# pnuematic_board_rev1.net
KiCad netlist of a schematic drawn in Altium Designer
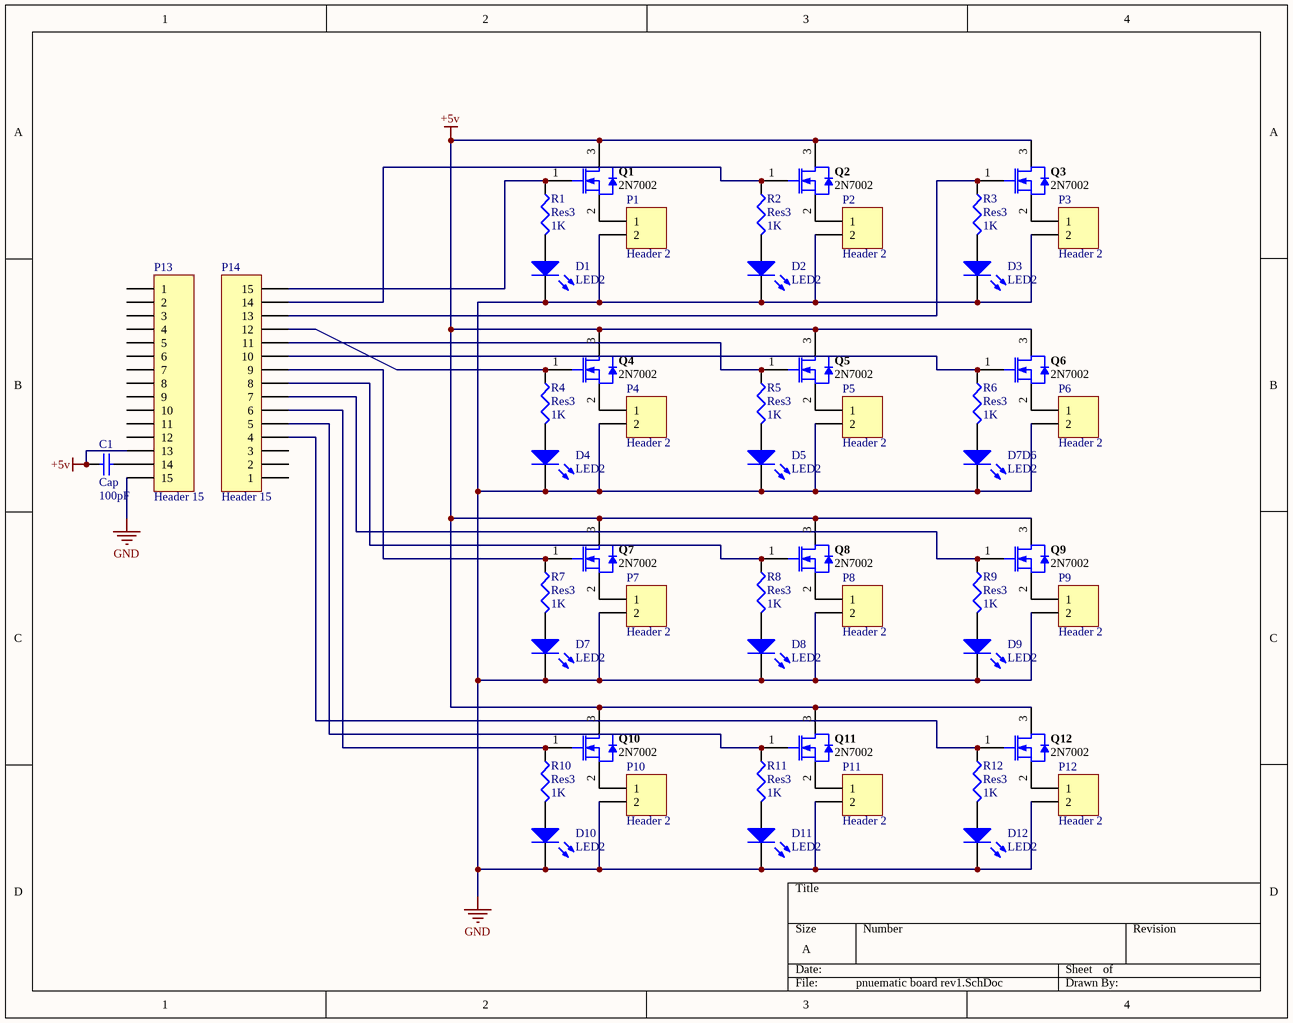
[diagram p0: pnuematic board rev1.SchDoc]

(export (version "E")
  (design (tool "Eeschema 10.0.6"))
  (components
    (comp (ref "C1")
      (value "Cap")
      (footprint "RAD-0.3")
      (description "Capacitor")
      (fields (field (name "ALTIUM_VALUE") "100pF") (field (name "PUBLISHER") "Altium Limited"))
      (libsource (lib "Miscellaneous Devices") (part "Cap"))
    )
    (comp (ref "D1")
      (value "LED2")
      (footprint "3.2X1.6X1.1")
      (description "Typical RED, GREEN, YELLOW, AMBER GaAs LED")
      (fields (field (name "PUBLISHER") "Altium Limited"))
      (libsource (lib "Miscellaneous Devices") (part "LED2"))
    )
    (comp (ref "D2")
      (value "LED2")
      (footprint "3.2X1.6X1.1")
      (description "Typical RED, GREEN, YELLOW, AMBER GaAs LED")
      (fields (field (name "PUBLISHER") "Altium Limited"))
      (libsource (lib "Miscellaneous Devices") (part "LED2"))
    )
    (comp (ref "D3")
      (value "LED2")
      (footprint "3.2X1.6X1.1")
      (description "Typical RED, GREEN, YELLOW, AMBER GaAs LED")
      (fields (field (name "PUBLISHER") "Altium Limited"))
      (libsource (lib "Miscellaneous Devices") (part "LED2"))
    )
    (comp (ref "D4")
      (value "LED2")
      (footprint "3.2X1.6X1.1")
      (description "Typical RED, GREEN, YELLOW, AMBER GaAs LED")
      (fields (field (name "PUBLISHER") "Altium Limited"))
      (libsource (lib "Miscellaneous Devices") (part "LED2"))
    )
    (comp (ref "D5")
      (value "LED2")
      (footprint "3.2X1.6X1.1")
      (description "Typical RED, GREEN, YELLOW, AMBER GaAs LED")
      (fields (field (name "PUBLISHER") "Altium Limited"))
      (libsource (lib "Miscellaneous Devices") (part "LED2"))
    )
    (comp (ref "D7")
      (value "LED2")
      (footprint "3.2X1.6X1.1")
      (description "Typical RED, GREEN, YELLOW, AMBER GaAs LED")
      (fields (field (name "PUBLISHER") "Altium Limited"))
      (libsource (lib "Miscellaneous Devices") (part "LED2"))
    )
    (comp (ref "D7D6")
      (value "LED2")
      (footprint "3.2X1.6X1.1")
      (description "Typical RED, GREEN, YELLOW, AMBER GaAs LED")
      (fields (field (name "PUBLISHER") "Altium Limited"))
      (libsource (lib "Miscellaneous Devices") (part "LED2"))
    )
    (comp (ref "D8")
      (value "LED2")
      (footprint "3.2X1.6X1.1")
      (description "Typical RED, GREEN, YELLOW, AMBER GaAs LED")
      (fields (field (name "PUBLISHER") "Altium Limited"))
      (libsource (lib "Miscellaneous Devices") (part "LED2"))
    )
    (comp (ref "D9")
      (value "LED2")
      (footprint "3.2X1.6X1.1")
      (description "Typical RED, GREEN, YELLOW, AMBER GaAs LED")
      (fields (field (name "PUBLISHER") "Altium Limited"))
      (libsource (lib "Miscellaneous Devices") (part "LED2"))
    )
    (comp (ref "D10")
      (value "LED2")
      (footprint "3.2X1.6X1.1")
      (description "Typical RED, GREEN, YELLOW, AMBER GaAs LED")
      (fields (field (name "PUBLISHER") "Altium Limited"))
      (libsource (lib "Miscellaneous Devices") (part "LED2"))
    )
    (comp (ref "D11")
      (value "LED2")
      (footprint "3.2X1.6X1.1")
      (description "Typical RED, GREEN, YELLOW, AMBER GaAs LED")
      (fields (field (name "PUBLISHER") "Altium Limited"))
      (libsource (lib "Miscellaneous Devices") (part "LED2"))
    )
    (comp (ref "D12")
      (value "LED2")
      (footprint "3.2X1.6X1.1")
      (description "Typical RED, GREEN, YELLOW, AMBER GaAs LED")
      (fields (field (name "PUBLISHER") "Altium Limited"))
      (libsource (lib "Miscellaneous Devices") (part "LED2"))
    )
    (comp (ref "P1")
      (value "Header 2")
      (footprint "HDR1X2")
      (description "Header, 2-Pin")
      (fields (field (name "PUBLISHER") "Altium Limited"))
      (libsource (lib "Miscellaneous Connectors") (part "Header 2"))
    )
    (comp (ref "P2")
      (value "Header 2")
      (footprint "HDR1X2")
      (description "Header, 2-Pin")
      (fields (field (name "PUBLISHER") "Altium Limited"))
      (libsource (lib "Miscellaneous Connectors") (part "Header 2"))
    )
    (comp (ref "P3")
      (value "Header 2")
      (footprint "HDR1X2")
      (description "Header, 2-Pin")
      (fields (field (name "PUBLISHER") "Altium Limited"))
      (libsource (lib "Miscellaneous Connectors") (part "Header 2"))
    )
    (comp (ref "P4")
      (value "Header 2")
      (footprint "HDR1X2")
      (description "Header, 2-Pin")
      (fields (field (name "PUBLISHER") "Altium Limited"))
      (libsource (lib "Miscellaneous Connectors") (part "Header 2"))
    )
    (comp (ref "P5")
      (value "Header 2")
      (footprint "HDR1X2")
      (description "Header, 2-Pin")
      (fields (field (name "PUBLISHER") "Altium Limited"))
      (libsource (lib "Miscellaneous Connectors") (part "Header 2"))
    )
    (comp (ref "P6")
      (value "Header 2")
      (footprint "HDR1X2")
      (description "Header, 2-Pin")
      (fields (field (name "PUBLISHER") "Altium Limited"))
      (libsource (lib "Miscellaneous Connectors") (part "Header 2"))
    )
    (comp (ref "P7")
      (value "Header 2")
      (footprint "HDR1X2")
      (description "Header, 2-Pin")
      (fields (field (name "PUBLISHER") "Altium Limited"))
      (libsource (lib "Miscellaneous Connectors") (part "Header 2"))
    )
    (comp (ref "P8")
      (value "Header 2")
      (footprint "HDR1X2")
      (description "Header, 2-Pin")
      (fields (field (name "PUBLISHER") "Altium Limited"))
      (libsource (lib "Miscellaneous Connectors") (part "Header 2"))
    )
    (comp (ref "P9")
      (value "Header 2")
      (footprint "HDR1X2")
      (description "Header, 2-Pin")
      (fields (field (name "PUBLISHER") "Altium Limited"))
      (libsource (lib "Miscellaneous Connectors") (part "Header 2"))
    )
    (comp (ref "P10")
      (value "Header 2")
      (footprint "HDR1X2")
      (description "Header, 2-Pin")
      (fields (field (name "PUBLISHER") "Altium Limited"))
      (libsource (lib "Miscellaneous Connectors") (part "Header 2"))
    )
    (comp (ref "P11")
      (value "Header 2")
      (footprint "HDR1X2")
      (description "Header, 2-Pin")
      (fields (field (name "PUBLISHER") "Altium Limited"))
      (libsource (lib "Miscellaneous Connectors") (part "Header 2"))
    )
    (comp (ref "P12")
      (value "Header 2")
      (footprint "HDR1X2")
      (description "Header, 2-Pin")
      (fields (field (name "PUBLISHER") "Altium Limited"))
      (libsource (lib "Miscellaneous Connectors") (part "Header 2"))
    )
    (comp (ref "P13")
      (value "Header 15")
      (footprint "HDR1X15")
      (description "Header, 15-Pin")
      (fields (field (name "PUBLISHER") "Altium Limited"))
      (libsource (lib "") (part "Header 15_1"))
    )
    (comp (ref "P14")
      (value "Header 15")
      (footprint "HDR1X15")
      (description "Header, 15-Pin")
      (fields (field (name "PUBLISHER") "Altium Limited"))
      (libsource (lib "Miscellaneous Connectors") (part "Header 15"))
    )
    (comp (ref "Q1")
      (value "2N7002")
      (footprint "INF-PG-SOT23_N")
      (fields (field (name "MANUFACTURER") "Infineon"))
      (libsource (lib "Infineon_Power_MOSFET") (part "2N7002"))
    )
    (comp (ref "Q2")
      (value "2N7002")
      (footprint "INF-PG-SOT23_N")
      (fields (field (name "MANUFACTURER") "Infineon"))
      (libsource (lib "Infineon_Power_MOSFET") (part "2N7002"))
    )
    (comp (ref "Q3")
      (value "2N7002")
      (footprint "INF-PG-SOT23_N")
      (fields (field (name "MANUFACTURER") "Infineon"))
      (libsource (lib "Infineon_Power_MOSFET") (part "2N7002"))
    )
    (comp (ref "Q4")
      (value "2N7002")
      (footprint "INF-PG-SOT23_N")
      (fields (field (name "MANUFACTURER") "Infineon"))
      (libsource (lib "Infineon_Power_MOSFET") (part "2N7002"))
    )
    (comp (ref "Q5")
      (value "2N7002")
      (footprint "INF-PG-SOT23_N")
      (fields (field (name "MANUFACTURER") "Infineon"))
      (libsource (lib "Infineon_Power_MOSFET") (part "2N7002"))
    )
    (comp (ref "Q6")
      (value "2N7002")
      (footprint "INF-PG-SOT23_N")
      (fields (field (name "MANUFACTURER") "Infineon"))
      (libsource (lib "Infineon_Power_MOSFET") (part "2N7002"))
    )
    (comp (ref "Q7")
      (value "2N7002")
      (footprint "INF-PG-SOT23_N")
      (fields (field (name "MANUFACTURER") "Infineon"))
      (libsource (lib "Infineon_Power_MOSFET") (part "2N7002"))
    )
    (comp (ref "Q8")
      (value "2N7002")
      (footprint "INF-PG-SOT23_N")
      (fields (field (name "MANUFACTURER") "Infineon"))
      (libsource (lib "Infineon_Power_MOSFET") (part "2N7002"))
    )
    (comp (ref "Q9")
      (value "2N7002")
      (footprint "INF-PG-SOT23_N")
      (fields (field (name "MANUFACTURER") "Infineon"))
      (libsource (lib "Infineon_Power_MOSFET") (part "2N7002"))
    )
    (comp (ref "Q10")
      (value "2N7002")
      (footprint "INF-PG-SOT23_N")
      (fields (field (name "MANUFACTURER") "Infineon"))
      (libsource (lib "Infineon_Power_MOSFET") (part "2N7002"))
    )
    (comp (ref "Q11")
      (value "2N7002")
      (footprint "INF-PG-SOT23_N")
      (fields (field (name "MANUFACTURER") "Infineon"))
      (libsource (lib "Infineon_Power_MOSFET") (part "2N7002"))
    )
    (comp (ref "Q12")
      (value "2N7002")
      (footprint "INF-PG-SOT23_N")
      (fields (field (name "MANUFACTURER") "Infineon"))
      (libsource (lib "Infineon_Power_MOSFET") (part "2N7002"))
    )
    (comp (ref "R1")
      (value "Res3")
      (footprint "J1-0603")
      (description "Resistor")
      (fields (field (name "ALTIUM_VALUE") "1K") (field (name "PUBLISHER") "Altium Limited"))
      (libsource (lib "Miscellaneous Devices") (part "Res3"))
    )
    (comp (ref "R2")
      (value "Res3")
      (footprint "J1-0603")
      (description "Resistor")
      (fields (field (name "ALTIUM_VALUE") "1K") (field (name "PUBLISHER") "Altium Limited"))
      (libsource (lib "Miscellaneous Devices") (part "Res3"))
    )
    (comp (ref "R3")
      (value "Res3")
      (footprint "J1-0603")
      (description "Resistor")
      (fields (field (name "ALTIUM_VALUE") "1K") (field (name "PUBLISHER") "Altium Limited"))
      (libsource (lib "Miscellaneous Devices") (part "Res3"))
    )
    (comp (ref "R4")
      (value "Res3")
      (footprint "J1-0603")
      (description "Resistor")
      (fields (field (name "ALTIUM_VALUE") "1K") (field (name "PUBLISHER") "Altium Limited"))
      (libsource (lib "Miscellaneous Devices") (part "Res3"))
    )
    (comp (ref "R5")
      (value "Res3")
      (footprint "J1-0603")
      (description "Resistor")
      (fields (field (name "ALTIUM_VALUE") "1K") (field (name "PUBLISHER") "Altium Limited"))
      (libsource (lib "Miscellaneous Devices") (part "Res3"))
    )
    (comp (ref "R6")
      (value "Res3")
      (footprint "J1-0603")
      (description "Resistor")
      (fields (field (name "ALTIUM_VALUE") "1K") (field (name "PUBLISHER") "Altium Limited"))
      (libsource (lib "Miscellaneous Devices") (part "Res3"))
    )
    (comp (ref "R7")
      (value "Res3")
      (footprint "J1-0603")
      (description "Resistor")
      (fields (field (name "ALTIUM_VALUE") "1K") (field (name "PUBLISHER") "Altium Limited"))
      (libsource (lib "Miscellaneous Devices") (part "Res3"))
    )
    (comp (ref "R8")
      (value "Res3")
      (footprint "J1-0603")
      (description "Resistor")
      (fields (field (name "ALTIUM_VALUE") "1K") (field (name "PUBLISHER") "Altium Limited"))
      (libsource (lib "Miscellaneous Devices") (part "Res3"))
    )
    (comp (ref "R9")
      (value "Res3")
      (footprint "J1-0603")
      (description "Resistor")
      (fields (field (name "ALTIUM_VALUE") "1K") (field (name "PUBLISHER") "Altium Limited"))
      (libsource (lib "Miscellaneous Devices") (part "Res3"))
    )
    (comp (ref "R10")
      (value "Res3")
      (footprint "J1-0603")
      (description "Resistor")
      (fields (field (name "ALTIUM_VALUE") "1K") (field (name "PUBLISHER") "Altium Limited"))
      (libsource (lib "Miscellaneous Devices") (part "Res3"))
    )
    (comp (ref "R11")
      (value "Res3")
      (footprint "J1-0603")
      (description "Resistor")
      (fields (field (name "ALTIUM_VALUE") "1K") (field (name "PUBLISHER") "Altium Limited"))
      (libsource (lib "Miscellaneous Devices") (part "Res3"))
    )
    (comp (ref "R12")
      (value "Res3")
      (footprint "J1-0603")
      (description "Resistor")
      (fields (field (name "ALTIUM_VALUE") "1K") (field (name "PUBLISHER") "Altium Limited"))
      (libsource (lib "Miscellaneous Devices") (part "Res3"))
    )
  )
  (nets
    (net (code "1") (name "+5v") (class "Default")
      (node (ref "C1") (pin "1") (pinfunction "1_1") (pintype "passive"))
      (node (ref "P13") (pin "13") (pinfunction "13_13") (pintype "passive"))
      (node (ref "Q1") (pin "3") (pinfunction "DRAIN_3") (pintype "passive"))
      (node (ref "Q10") (pin "3") (pinfunction "DRAIN_3") (pintype "passive"))
      (node (ref "Q11") (pin "3") (pinfunction "DRAIN_3") (pintype "passive"))
      (node (ref "Q12") (pin "3") (pinfunction "DRAIN_3") (pintype "passive"))
      (node (ref "Q2") (pin "3") (pinfunction "DRAIN_3") (pintype "passive"))
      (node (ref "Q3") (pin "3") (pinfunction "DRAIN_3") (pintype "passive"))
      (node (ref "Q4") (pin "3") (pinfunction "DRAIN_3") (pintype "passive"))
      (node (ref "Q5") (pin "3") (pinfunction "DRAIN_3") (pintype "passive"))
      (node (ref "Q6") (pin "3") (pinfunction "DRAIN_3") (pintype "passive"))
      (node (ref "Q7") (pin "3") (pinfunction "DRAIN_3") (pintype "passive"))
      (node (ref "Q8") (pin "3") (pinfunction "DRAIN_3") (pintype "passive"))
      (node (ref "Q9") (pin "3") (pinfunction "DRAIN_3") (pintype "passive"))
    )
    (net (code "2") (name "GND") (class "Default")
      (node (ref "D1") (pin "2") (pinfunction "K_2") (pintype "passive"))
      (node (ref "D10") (pin "2") (pinfunction "K_2") (pintype "passive"))
      (node (ref "D11") (pin "2") (pinfunction "K_2") (pintype "passive"))
      (node (ref "D12") (pin "2") (pinfunction "K_2") (pintype "passive"))
      (node (ref "D2") (pin "2") (pinfunction "K_2") (pintype "passive"))
      (node (ref "D3") (pin "2") (pinfunction "K_2") (pintype "passive"))
      (node (ref "D4") (pin "2") (pinfunction "K_2") (pintype "passive"))
      (node (ref "D5") (pin "2") (pinfunction "K_2") (pintype "passive"))
      (node (ref "D7") (pin "2") (pinfunction "K_2") (pintype "passive"))
      (node (ref "D7D6") (pin "2") (pinfunction "K_2") (pintype "passive"))
      (node (ref "D8") (pin "2") (pinfunction "K_2") (pintype "passive"))
      (node (ref "D9") (pin "2") (pinfunction "K_2") (pintype "passive"))
      (node (ref "P1") (pin "2") (pinfunction "2_2") (pintype "passive"))
      (node (ref "P10") (pin "2") (pinfunction "2_2") (pintype "passive"))
      (node (ref "P11") (pin "2") (pinfunction "2_2") (pintype "passive"))
      (node (ref "P12") (pin "2") (pinfunction "2_2") (pintype "passive"))
      (node (ref "P13") (pin "15") (pinfunction "15_15") (pintype "passive"))
      (node (ref "P2") (pin "2") (pinfunction "2_2") (pintype "passive"))
      (node (ref "P3") (pin "2") (pinfunction "2_2") (pintype "passive"))
      (node (ref "P4") (pin "2") (pinfunction "2_2") (pintype "passive"))
      (node (ref "P5") (pin "2") (pinfunction "2_2") (pintype "passive"))
      (node (ref "P6") (pin "2") (pinfunction "2_2") (pintype "passive"))
      (node (ref "P7") (pin "2") (pinfunction "2_2") (pintype "passive"))
      (node (ref "P8") (pin "2") (pinfunction "2_2") (pintype "passive"))
      (node (ref "P9") (pin "2") (pinfunction "2_2") (pintype "passive"))
    )
    (net (code "3") (name "Net-(C1-Pad2)") (class "Default")
      (node (ref "C1") (pin "2") (pinfunction "2_2") (pintype "passive"))
      (node (ref "P13") (pin "14") (pinfunction "14_14") (pintype "passive"))
    )
    (net (code "4") (name "Net-(Q1-GATE)") (class "Default")
      (node (ref "P14") (pin "15") (pinfunction "15_15") (pintype "passive"))
      (node (ref "Q1") (pin "1") (pinfunction "GATE_1") (pintype "passive"))
      (node (ref "R1") (pin "1") (pinfunction "1_1") (pintype "passive"))
    )
    (net (code "5") (name "Net-(Q1-SOURCE)") (class "Default")
      (node (ref "P1") (pin "1") (pinfunction "1_1") (pintype "passive"))
      (node (ref "Q1") (pin "2") (pinfunction "SOURCE_2") (pintype "passive"))
    )
    (net (code "6") (name "Net-(Q2-GATE)") (class "Default")
      (node (ref "P14") (pin "14") (pinfunction "14_14") (pintype "passive"))
      (node (ref "Q2") (pin "1") (pinfunction "GATE_1") (pintype "passive"))
      (node (ref "R2") (pin "1") (pinfunction "1_1") (pintype "passive"))
    )
    (net (code "7") (name "Net-(Q2-SOURCE)") (class "Default")
      (node (ref "P2") (pin "1") (pinfunction "1_1") (pintype "passive"))
      (node (ref "Q2") (pin "2") (pinfunction "SOURCE_2") (pintype "passive"))
    )
    (net (code "8") (name "Net-(Q3-GATE)") (class "Default")
      (node (ref "P14") (pin "13") (pinfunction "13_13") (pintype "passive"))
      (node (ref "Q3") (pin "1") (pinfunction "GATE_1") (pintype "passive"))
      (node (ref "R3") (pin "1") (pinfunction "1_1") (pintype "passive"))
    )
    (net (code "9") (name "Net-(Q3-SOURCE)") (class "Default")
      (node (ref "P3") (pin "1") (pinfunction "1_1") (pintype "passive"))
      (node (ref "Q3") (pin "2") (pinfunction "SOURCE_2") (pintype "passive"))
    )
    (net (code "10") (name "Net-(Q4-GATE)") (class "Default")
      (node (ref "P14") (pin "12") (pinfunction "12_12") (pintype "passive"))
      (node (ref "Q4") (pin "1") (pinfunction "GATE_1") (pintype "passive"))
      (node (ref "R4") (pin "1") (pinfunction "1_1") (pintype "passive"))
    )
    (net (code "11") (name "Net-(Q4-SOURCE)") (class "Default")
      (node (ref "P4") (pin "1") (pinfunction "1_1") (pintype "passive"))
      (node (ref "Q4") (pin "2") (pinfunction "SOURCE_2") (pintype "passive"))
    )
    (net (code "12") (name "Net-(Q5-GATE)") (class "Default")
      (node (ref "P14") (pin "11") (pinfunction "11_11") (pintype "passive"))
      (node (ref "Q5") (pin "1") (pinfunction "GATE_1") (pintype "passive"))
      (node (ref "R5") (pin "1") (pinfunction "1_1") (pintype "passive"))
    )
    (net (code "13") (name "Net-(Q5-SOURCE)") (class "Default")
      (node (ref "P5") (pin "1") (pinfunction "1_1") (pintype "passive"))
      (node (ref "Q5") (pin "2") (pinfunction "SOURCE_2") (pintype "passive"))
    )
    (net (code "14") (name "Net-(Q6-GATE)") (class "Default")
      (node (ref "P14") (pin "10") (pinfunction "10_10") (pintype "passive"))
      (node (ref "Q6") (pin "1") (pinfunction "GATE_1") (pintype "passive"))
      (node (ref "R6") (pin "1") (pinfunction "1_1") (pintype "passive"))
    )
    (net (code "15") (name "Net-(Q6-SOURCE)") (class "Default")
      (node (ref "P6") (pin "1") (pinfunction "1_1") (pintype "passive"))
      (node (ref "Q6") (pin "2") (pinfunction "SOURCE_2") (pintype "passive"))
    )
    (net (code "16") (name "Net-(Q7-GATE)") (class "Default")
      (node (ref "P14") (pin "9") (pinfunction "9_9") (pintype "passive"))
      (node (ref "Q7") (pin "1") (pinfunction "GATE_1") (pintype "passive"))
      (node (ref "R7") (pin "1") (pinfunction "1_1") (pintype "passive"))
    )
    (net (code "17") (name "Net-(Q7-SOURCE)") (class "Default")
      (node (ref "P7") (pin "1") (pinfunction "1_1") (pintype "passive"))
      (node (ref "Q7") (pin "2") (pinfunction "SOURCE_2") (pintype "passive"))
    )
    (net (code "18") (name "Net-(Q8-GATE)") (class "Default")
      (node (ref "P14") (pin "8") (pinfunction "8_8") (pintype "passive"))
      (node (ref "Q8") (pin "1") (pinfunction "GATE_1") (pintype "passive"))
      (node (ref "R8") (pin "1") (pinfunction "1_1") (pintype "passive"))
    )
    (net (code "19") (name "Net-(Q8-SOURCE)") (class "Default")
      (node (ref "P8") (pin "1") (pinfunction "1_1") (pintype "passive"))
      (node (ref "Q8") (pin "2") (pinfunction "SOURCE_2") (pintype "passive"))
    )
    (net (code "20") (name "Net-(Q9-GATE)") (class "Default")
      (node (ref "P14") (pin "7") (pinfunction "7_7") (pintype "passive"))
      (node (ref "Q9") (pin "1") (pinfunction "GATE_1") (pintype "passive"))
      (node (ref "R9") (pin "1") (pinfunction "1_1") (pintype "passive"))
    )
    (net (code "21") (name "Net-(Q9-SOURCE)") (class "Default")
      (node (ref "P9") (pin "1") (pinfunction "1_1") (pintype "passive"))
      (node (ref "Q9") (pin "2") (pinfunction "SOURCE_2") (pintype "passive"))
    )
    (net (code "22") (name "Net-(Q10-GATE)") (class "Default")
      (node (ref "P14") (pin "6") (pinfunction "6_6") (pintype "passive"))
      (node (ref "Q10") (pin "1") (pinfunction "GATE_1") (pintype "passive"))
      (node (ref "R10") (pin "1") (pinfunction "1_1") (pintype "passive"))
    )
    (net (code "23") (name "Net-(Q10-SOURCE)") (class "Default")
      (node (ref "P10") (pin "1") (pinfunction "1_1") (pintype "passive"))
      (node (ref "Q10") (pin "2") (pinfunction "SOURCE_2") (pintype "passive"))
    )
    (net (code "24") (name "Net-(Q11-GATE)") (class "Default")
      (node (ref "P14") (pin "5") (pinfunction "5_5") (pintype "passive"))
      (node (ref "Q11") (pin "1") (pinfunction "GATE_1") (pintype "passive"))
      (node (ref "R11") (pin "1") (pinfunction "1_1") (pintype "passive"))
    )
    (net (code "25") (name "Net-(Q11-SOURCE)") (class "Default")
      (node (ref "P11") (pin "1") (pinfunction "1_1") (pintype "passive"))
      (node (ref "Q11") (pin "2") (pinfunction "SOURCE_2") (pintype "passive"))
    )
    (net (code "26") (name "Net-(Q12-GATE)") (class "Default")
      (node (ref "P14") (pin "4") (pinfunction "4_4") (pintype "passive"))
      (node (ref "Q12") (pin "1") (pinfunction "GATE_1") (pintype "passive"))
      (node (ref "R12") (pin "1") (pinfunction "1_1") (pintype "passive"))
    )
    (net (code "27") (name "Net-(Q12-SOURCE)") (class "Default")
      (node (ref "P12") (pin "1") (pinfunction "1_1") (pintype "passive"))
      (node (ref "Q12") (pin "2") (pinfunction "SOURCE_2") (pintype "passive"))
    )
    (net (code "28") (name "unconnected-(D1-A-Pad1)") (class "Default")
      (node (ref "D1") (pin "1") (pinfunction "A_1") (pintype "passive"))
    )
    (net (code "29") (name "unconnected-(D2-A-Pad1)") (class "Default")
      (node (ref "D2") (pin "1") (pinfunction "A_1") (pintype "passive"))
    )
    (net (code "30") (name "unconnected-(D3-A-Pad1)") (class "Default")
      (node (ref "D3") (pin "1") (pinfunction "A_1") (pintype "passive"))
    )
    (net (code "31") (name "unconnected-(D4-A-Pad1)") (class "Default")
      (node (ref "D4") (pin "1") (pinfunction "A_1") (pintype "passive"))
    )
    (net (code "32") (name "unconnected-(D5-A-Pad1)") (class "Default")
      (node (ref "D5") (pin "1") (pinfunction "A_1") (pintype "passive"))
    )
    (net (code "33") (name "unconnected-(D7-A-Pad1)") (class "Default")
      (node (ref "D7") (pin "1") (pinfunction "A_1") (pintype "passive"))
    )
    (net (code "34") (name "unconnected-(D7D6-A-Pad1)") (class "Default")
      (node (ref "D7D6") (pin "1") (pinfunction "A_1") (pintype "passive"))
    )
    (net (code "35") (name "unconnected-(D8-A-Pad1)") (class "Default")
      (node (ref "D8") (pin "1") (pinfunction "A_1") (pintype "passive"))
    )
    (net (code "36") (name "unconnected-(D9-A-Pad1)") (class "Default")
      (node (ref "D9") (pin "1") (pinfunction "A_1") (pintype "passive"))
    )
    (net (code "37") (name "unconnected-(D10-A-Pad1)") (class "Default")
      (node (ref "D10") (pin "1") (pinfunction "A_1") (pintype "passive"))
    )
    (net (code "38") (name "unconnected-(D11-A-Pad1)") (class "Default")
      (node (ref "D11") (pin "1") (pinfunction "A_1") (pintype "passive"))
    )
    (net (code "39") (name "unconnected-(D12-A-Pad1)") (class "Default")
      (node (ref "D12") (pin "1") (pinfunction "A_1") (pintype "passive"))
    )
    (net (code "40") (name "unconnected-(P13-Pad1)") (class "Default")
      (node (ref "P13") (pin "1") (pinfunction "1_1") (pintype "passive"))
    )
    (net (code "41") (name "unconnected-(P13-Pad2)") (class "Default")
      (node (ref "P13") (pin "2") (pinfunction "2_2") (pintype "passive"))
    )
    (net (code "42") (name "unconnected-(P13-Pad3)") (class "Default")
      (node (ref "P13") (pin "3") (pinfunction "3_3") (pintype "passive"))
    )
    (net (code "43") (name "unconnected-(P13-Pad4)") (class "Default")
      (node (ref "P13") (pin "4") (pinfunction "4_4") (pintype "passive"))
    )
    (net (code "44") (name "unconnected-(P13-Pad5)") (class "Default")
      (node (ref "P13") (pin "5") (pinfunction "5_5") (pintype "passive"))
    )
    (net (code "45") (name "unconnected-(P13-Pad6)") (class "Default")
      (node (ref "P13") (pin "6") (pinfunction "6_6") (pintype "passive"))
    )
    (net (code "46") (name "unconnected-(P13-Pad7)") (class "Default")
      (node (ref "P13") (pin "7") (pinfunction "7_7") (pintype "passive"))
    )
    (net (code "47") (name "unconnected-(P13-Pad8)") (class "Default")
      (node (ref "P13") (pin "8") (pinfunction "8_8") (pintype "passive"))
    )
    (net (code "48") (name "unconnected-(P13-Pad9)") (class "Default")
      (node (ref "P13") (pin "9") (pinfunction "9_9") (pintype "passive"))
    )
    (net (code "49") (name "unconnected-(P13-Pad10)") (class "Default")
      (node (ref "P13") (pin "10") (pinfunction "10_10") (pintype "passive"))
    )
    (net (code "50") (name "unconnected-(P13-Pad11)") (class "Default")
      (node (ref "P13") (pin "11") (pinfunction "11_11") (pintype "passive"))
    )
    (net (code "51") (name "unconnected-(P13-Pad12)") (class "Default")
      (node (ref "P13") (pin "12") (pinfunction "12_12") (pintype "passive"))
    )
    (net (code "52") (name "unconnected-(P14-Pad1)") (class "Default")
      (node (ref "P14") (pin "1") (pinfunction "1_1") (pintype "passive"))
    )
    (net (code "53") (name "unconnected-(P14-Pad2)") (class "Default")
      (node (ref "P14") (pin "2") (pinfunction "2_2") (pintype "passive"))
    )
    (net (code "54") (name "unconnected-(P14-Pad3)") (class "Default")
      (node (ref "P14") (pin "3") (pinfunction "3_3") (pintype "passive"))
    )
    (net (code "55") (name "unconnected-(R1-Pad2)") (class "Default")
      (node (ref "R1") (pin "2") (pinfunction "2_2") (pintype "passive"))
    )
    (net (code "56") (name "unconnected-(R2-Pad2)") (class "Default")
      (node (ref "R2") (pin "2") (pinfunction "2_2") (pintype "passive"))
    )
    (net (code "57") (name "unconnected-(R3-Pad2)") (class "Default")
      (node (ref "R3") (pin "2") (pinfunction "2_2") (pintype "passive"))
    )
    (net (code "58") (name "unconnected-(R4-Pad2)") (class "Default")
      (node (ref "R4") (pin "2") (pinfunction "2_2") (pintype "passive"))
    )
    (net (code "59") (name "unconnected-(R5-Pad2)") (class "Default")
      (node (ref "R5") (pin "2") (pinfunction "2_2") (pintype "passive"))
    )
    (net (code "60") (name "unconnected-(R6-Pad2)") (class "Default")
      (node (ref "R6") (pin "2") (pinfunction "2_2") (pintype "passive"))
    )
    (net (code "61") (name "unconnected-(R7-Pad2)") (class "Default")
      (node (ref "R7") (pin "2") (pinfunction "2_2") (pintype "passive"))
    )
    (net (code "62") (name "unconnected-(R8-Pad2)") (class "Default")
      (node (ref "R8") (pin "2") (pinfunction "2_2") (pintype "passive"))
    )
    (net (code "63") (name "unconnected-(R9-Pad2)") (class "Default")
      (node (ref "R9") (pin "2") (pinfunction "2_2") (pintype "passive"))
    )
    (net (code "64") (name "unconnected-(R10-Pad2)") (class "Default")
      (node (ref "R10") (pin "2") (pinfunction "2_2") (pintype "passive"))
    )
    (net (code "65") (name "unconnected-(R11-Pad2)") (class "Default")
      (node (ref "R11") (pin "2") (pinfunction "2_2") (pintype "passive"))
    )
    (net (code "66") (name "unconnected-(R12-Pad2)") (class "Default")
      (node (ref "R12") (pin "2") (pinfunction "2_2") (pintype "passive"))
    )
  )
)
